# Schematic_start_module_sumo_IR_V1_0.net
KiCad netlist of a schematic drawn in EAGLE
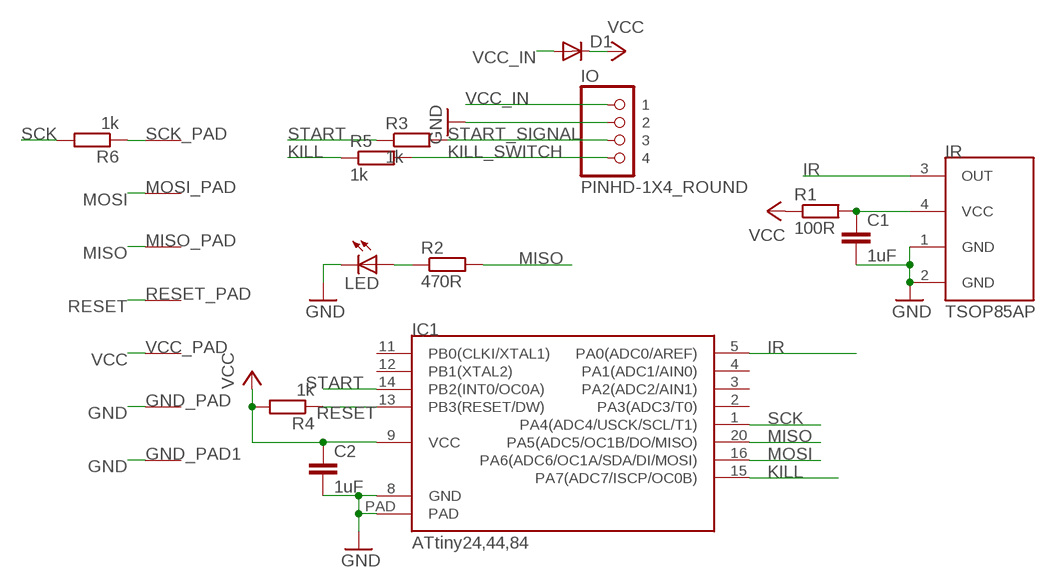
[diagram p0: schematic, sheet 1]

(export (version "E")
  (design (tool "Eeschema 10.0.6"))
  (components
    (comp (ref "C1")
      (value "1uF")
      (footprint "eagle-import:C0603")
      (libsource (lib "eagle-import") (part "C-EUC0603"))
    )
    (comp (ref "C2")
      (value "1uF")
      (footprint "eagle-import:C0603")
      (libsource (lib "eagle-import") (part "C-EUC0603"))
    )
    (comp (ref "D1")
      (value "DIODE-SOD523")
      (footprint "eagle-import:SOD523")
      (libsource (lib "eagle-import") (part "DIODE-SOD523"))
    )
    (comp (ref "GND_PAD")
      (value "PAD50X50")
      (footprint "eagle-import:PAD_50X50")
      (libsource (lib "eagle-import") (part "PAD50X50"))
    )
    (comp (ref "GND_PAD1")
      (value "PAD75X75")
      (footprint "eagle-import:PAD_75X75")
      (libsource (lib "eagle-import") (part "PAD75X75"))
    )
    (comp (ref "IC1")
      (value "ATTINY24,44,84_QFNVQFN")
      (footprint "eagle-import:VQFN20")
      (libsource (lib "eagle-import") (part "ATTINY24,44,84_QFNVQFN"))
    )
    (comp (ref "IO")
      (value "PINHD-1X4_ROUND")
      (footprint "eagle-import:1X04_ROUND")
      (libsource (lib "eagle-import") (part "PINHD-1X4_ROUND"))
    )
    (comp (ref "IR")
      (value "TSOP85AP")
      (footprint "eagle-import:TSOP85AP")
      (libsource (lib "eagle-import") (part "TSOP85AP"))
    )
    (comp (ref "LED")
      (value "LED0603")
      (footprint "eagle-import:0603_SMALL")
      (libsource (lib "eagle-import") (part "LED0603"))
    )
    (comp (ref "MISO_PAD")
      (value "mosi")
      (footprint "eagle-import:PAD_50X50")
      (libsource (lib "eagle-import") (part "PAD50X50"))
    )
    (comp (ref "MOSI_PAD")
      (value "PAD50X50")
      (footprint "eagle-import:PAD_50X50")
      (libsource (lib "eagle-import") (part "PAD50X50"))
    )
    (comp (ref "R1")
      (value "100R")
      (footprint "eagle-import:R0402")
      (libsource (lib "eagle-import") (part "R-EU_R0402"))
    )
    (comp (ref "R2")
      (value "470R")
      (footprint "eagle-import:R0402")
      (libsource (lib "eagle-import") (part "R-EU_R0402"))
    )
    (comp (ref "R3")
      (value "1k")
      (footprint "eagle-import:R0402")
      (libsource (lib "eagle-import") (part "R-EU_R0402"))
    )
    (comp (ref "R4")
      (value "1k")
      (footprint "eagle-import:R0402")
      (libsource (lib "eagle-import") (part "R-EU_R0402"))
    )
    (comp (ref "R5")
      (value "1k")
      (footprint "eagle-import:R0402")
      (libsource (lib "eagle-import") (part "R-EU_R0402"))
    )
    (comp (ref "R6")
      (value "1k")
      (footprint "eagle-import:R0402")
      (libsource (lib "eagle-import") (part "R-EU_R0402"))
    )
    (comp (ref "RESET_PAD")
      (value "PAD50X50")
      (footprint "eagle-import:PAD_50X50")
      (libsource (lib "eagle-import") (part "PAD50X50"))
    )
    (comp (ref "SCK_PAD")
      (value "PAD75X75")
      (footprint "eagle-import:PAD_75X75")
      (libsource (lib "eagle-import") (part "PAD75X75"))
    )
    (comp (ref "VCC_PAD")
      (value "PAD50X50")
      (footprint "eagle-import:PAD_50X50")
      (libsource (lib "eagle-import") (part "PAD50X50"))
    )
  )
  (nets
    (net (code "1") (name "/IR") (class "Default")
      (node (ref "IC1") (pin "5") (pinfunction "PA0(ADC0/AREF)_5") (pintype "bidirectional"))
      (node (ref "IR") (pin "3") (pinfunction "OUT_3") (pintype "bidirectional"))
    )
    (net (code "2") (name "/KILL") (class "Default")
      (node (ref "IC1") (pin "15") (pinfunction "PA7(ADC7/ISCP/OC0B)_15") (pintype "bidirectional"))
      (node (ref "R5") (pin "1") (pinfunction "1_1") (pintype "passive"))
    )
    (net (code "3") (name "/KILL_SWITCH") (class "Default")
      (node (ref "IO") (pin "4") (pinfunction "4_4") (pintype "passive"))
      (node (ref "R5") (pin "2") (pinfunction "2_2") (pintype "passive"))
    )
    (net (code "4") (name "/MISO") (class "Default")
      (node (ref "IC1") (pin "20") (pinfunction "PA5(ADC5/OC1B/DO/MISO)_20") (pintype "bidirectional"))
      (node (ref "MISO_PAD") (pin "P$1") (pinfunction "PAD_P$1") (pintype "power_in"))
      (node (ref "R2") (pin "2") (pinfunction "2_2") (pintype "passive"))
    )
    (net (code "5") (name "/MOSI") (class "Default")
      (node (ref "IC1") (pin "16") (pinfunction "PA6(ADC6/OC1A/SDA/DI/MOSI)_16") (pintype "bidirectional"))
      (node (ref "MOSI_PAD") (pin "P$1") (pinfunction "PAD_P$1") (pintype "power_in"))
    )
    (net (code "6") (name "/RESET") (class "Default")
      (node (ref "IC1") (pin "13") (pinfunction "PB3(RESET/DW)_13") (pintype "bidirectional"))
      (node (ref "R4") (pin "1") (pinfunction "1_1") (pintype "passive"))
      (node (ref "RESET_PAD") (pin "P$1") (pinfunction "PAD_P$1") (pintype "power_in"))
    )
    (net (code "7") (name "/SCK") (class "Default")
      (node (ref "IC1") (pin "1") (pinfunction "PA4(ADC4/USCK/SCL/T1)_1") (pintype "bidirectional"))
      (node (ref "R6") (pin "2") (pinfunction "2_2") (pintype "passive"))
    )
    (net (code "8") (name "/START") (class "Default")
      (node (ref "IC1") (pin "14") (pinfunction "PB2(INT0/OC0A)_14") (pintype "bidirectional"))
      (node (ref "R3") (pin "1") (pinfunction "1_1") (pintype "passive"))
    )
    (net (code "9") (name "/START_SIGNAL") (class "Default")
      (node (ref "IO") (pin "3") (pinfunction "3_3") (pintype "passive"))
      (node (ref "R3") (pin "2") (pinfunction "2_2") (pintype "passive"))
    )
    (net (code "10") (name "/VCC_IN") (class "Default")
      (node (ref "D1") (pin "A") (pinfunction "A_A") (pintype "passive"))
      (node (ref "IO") (pin "1") (pinfunction "1_1") (pintype "passive"))
    )
    (net (code "11") (name "GND") (class "Default")
      (node (ref "C1") (pin "2") (pinfunction "2_2") (pintype "passive"))
      (node (ref "C2") (pin "2") (pinfunction "2_2") (pintype "passive"))
      (node (ref "GND_PAD") (pin "P$1") (pinfunction "PAD_P$1") (pintype "power_in"))
      (node (ref "GND_PAD1") (pin "P$1") (pinfunction "PAD_P$1") (pintype "power_in"))
      (node (ref "IC1") (pin "8") (pinfunction "GND_8") (pintype "bidirectional"))
      (node (ref "IC1") (pin "PAD") (pinfunction "PAD_PAD") (pintype "bidirectional"))
      (node (ref "IO") (pin "2") (pinfunction "2_2") (pintype "passive"))
      (node (ref "IR") (pin "1") (pinfunction "GND_1") (pintype "bidirectional"))
      (node (ref "IR") (pin "2") (pinfunction "GND_2") (pintype "bidirectional"))
      (node (ref "LED") (pin "2") (pinfunction "C_2") (pintype "passive"))
    )
    (net (code "12") (name "Net-(IR-VCC)") (class "Default")
      (node (ref "C1") (pin "1") (pinfunction "1_1") (pintype "passive"))
      (node (ref "IR") (pin "4") (pinfunction "VCC_4") (pintype "bidirectional"))
      (node (ref "R1") (pin "2") (pinfunction "2_2") (pintype "passive"))
    )
    (net (code "13") (name "Net-(LED-A)") (class "Default")
      (node (ref "LED") (pin "1") (pinfunction "A_1") (pintype "passive"))
      (node (ref "R2") (pin "1") (pinfunction "1_1") (pintype "passive"))
    )
    (net (code "14") (name "Net-(SCK_PAD-PAD)") (class "Default")
      (node (ref "R6") (pin "1") (pinfunction "1_1") (pintype "passive"))
      (node (ref "SCK_PAD") (pin "P$1") (pinfunction "PAD_P$1") (pintype "power_in"))
    )
    (net (code "15") (name "VCC") (class "Default")
      (node (ref "C2") (pin "1") (pinfunction "1_1") (pintype "passive"))
      (node (ref "D1") (pin "C") (pinfunction "C_C") (pintype "passive"))
      (node (ref "IC1") (pin "9") (pinfunction "VCC_9") (pintype "bidirectional"))
      (node (ref "R1") (pin "1") (pinfunction "1_1") (pintype "passive"))
      (node (ref "R4") (pin "2") (pinfunction "2_2") (pintype "passive"))
      (node (ref "VCC_PAD") (pin "P$1") (pinfunction "PAD_P$1") (pintype "power_in"))
    )
    (net (code "16") (name "unconnected-(IC1-PA1(ADC1{slash}AIN0)-Pad4)") (class "Default")
      (node (ref "IC1") (pin "4") (pinfunction "PA1(ADC1/AIN0)_4") (pintype "bidirectional"))
    )
    (net (code "17") (name "unconnected-(IC1-PA2(ADC2{slash}AIN1)-Pad3)") (class "Default")
      (node (ref "IC1") (pin "3") (pinfunction "PA2(ADC2/AIN1)_3") (pintype "bidirectional"))
    )
    (net (code "18") (name "unconnected-(IC1-PA3(ADC3{slash}T0)-Pad2)") (class "Default")
      (node (ref "IC1") (pin "2") (pinfunction "PA3(ADC3/T0)_2") (pintype "bidirectional"))
    )
    (net (code "19") (name "unconnected-(IC1-PB0(CLKI{slash}XTAL1)-Pad11)") (class "Default")
      (node (ref "IC1") (pin "11") (pinfunction "PB0(CLKI/XTAL1)_11") (pintype "bidirectional"))
    )
    (net (code "20") (name "unconnected-(IC1-PB1(XTAL2)-Pad12)") (class "Default")
      (node (ref "IC1") (pin "12") (pinfunction "PB1(XTAL2)_12") (pintype "bidirectional"))
    )
  )
)
